# modulo_alimentador_schdoc.net
KiCad netlist of a schematic drawn in Altium Designer
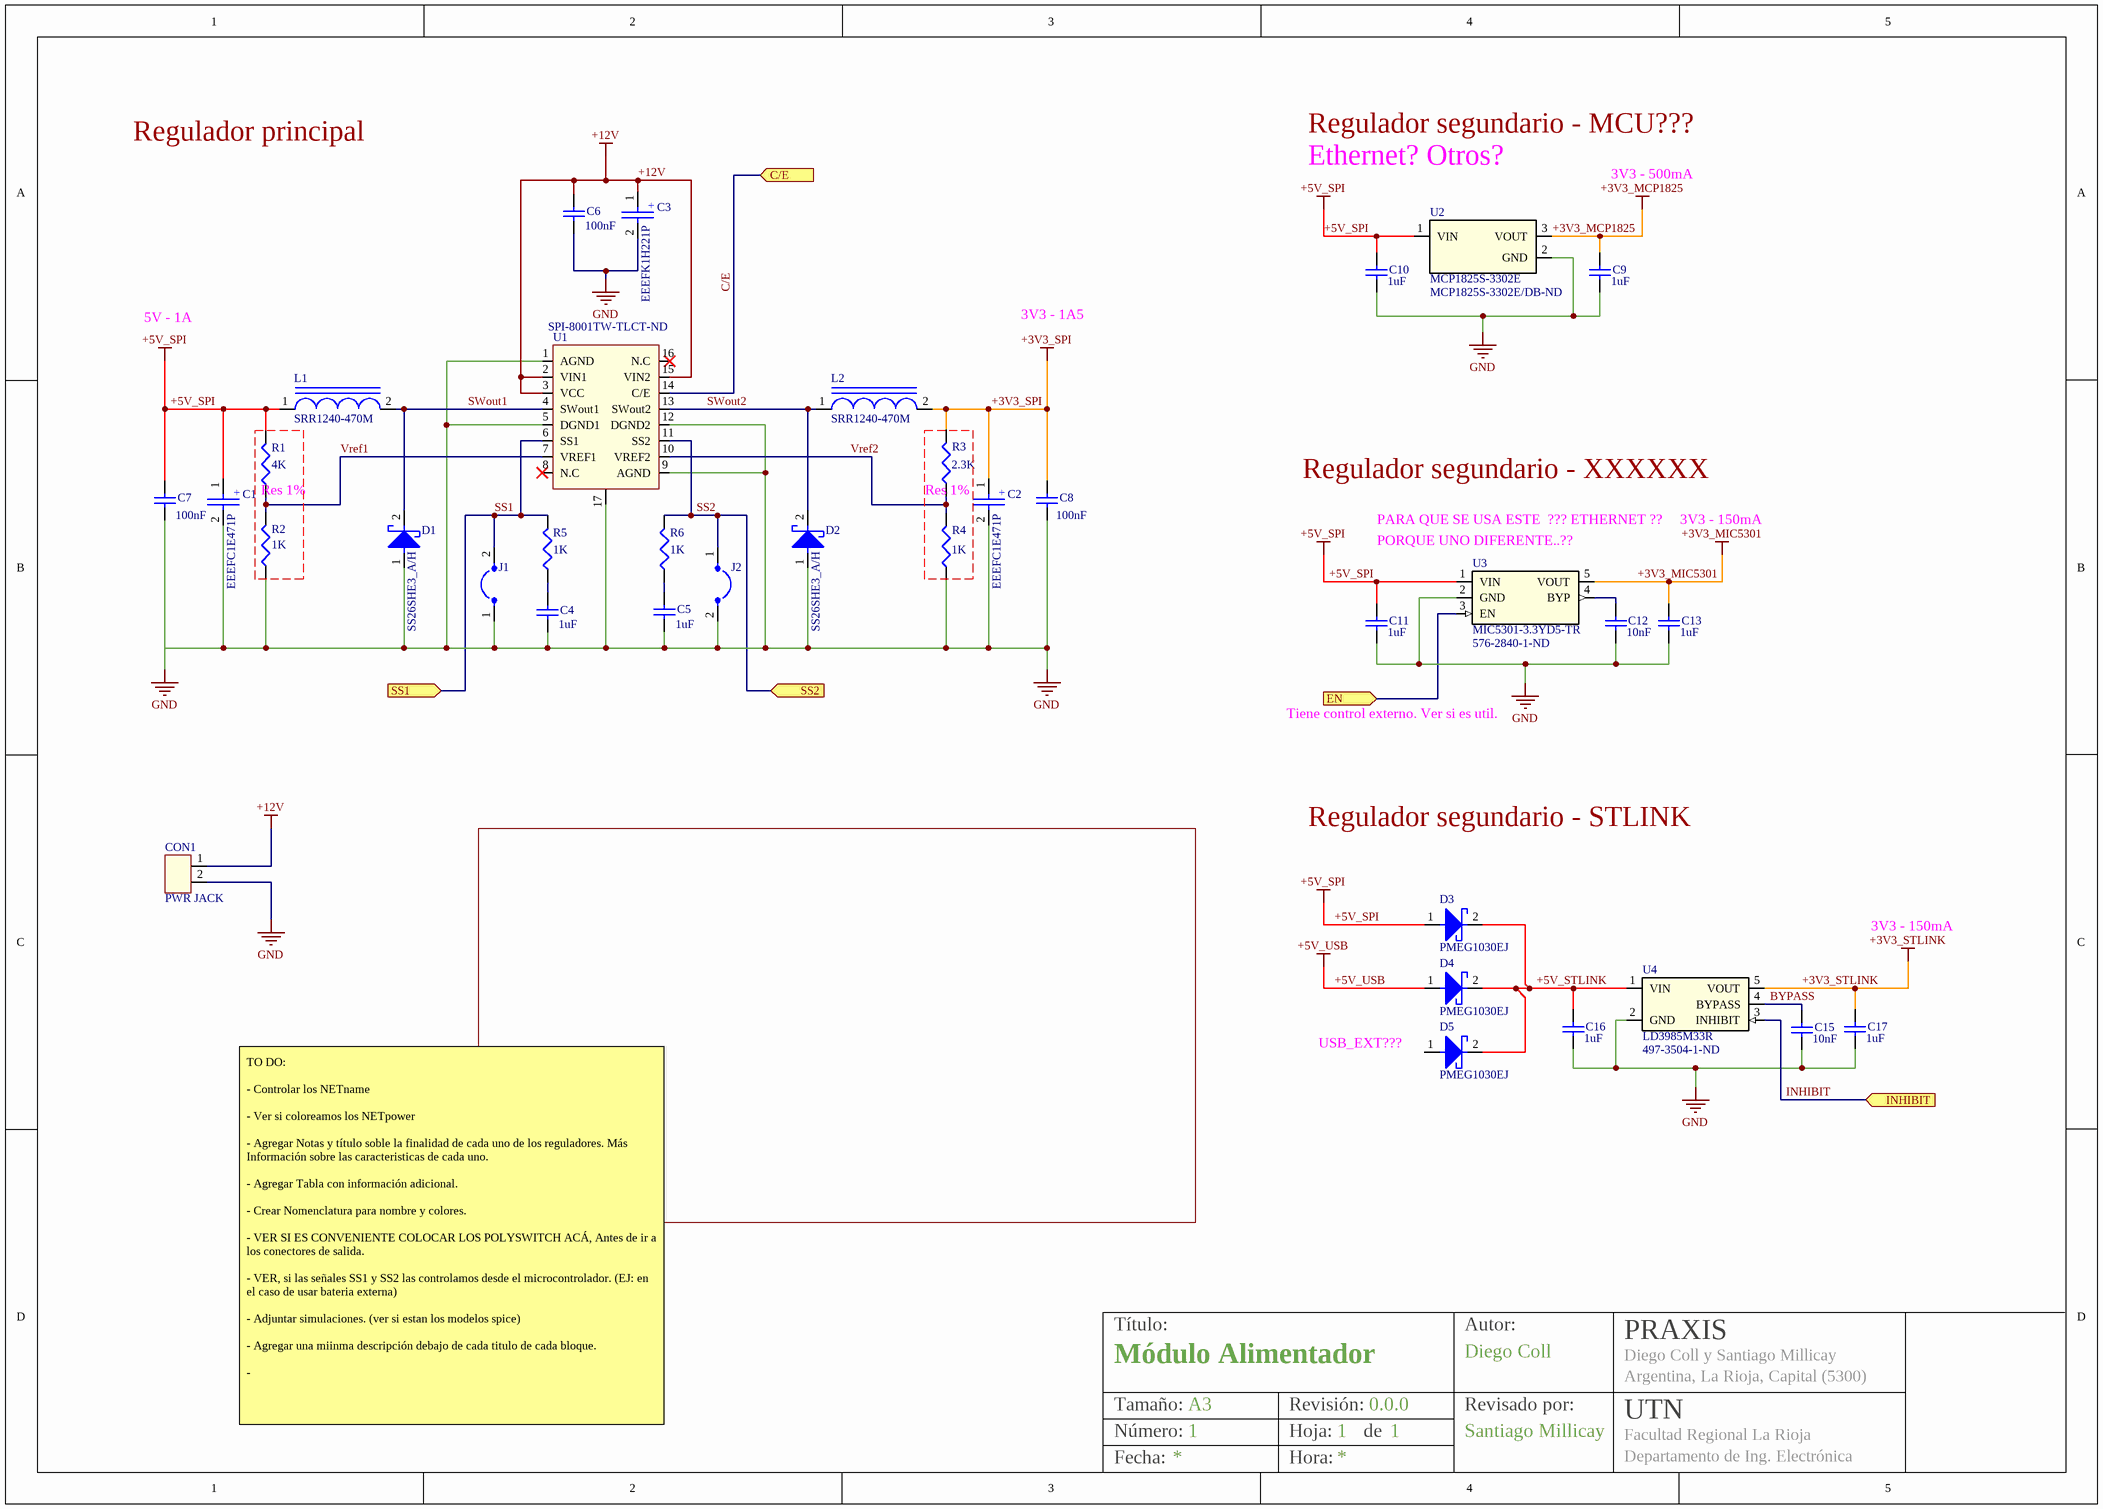
[diagram p0: modulo_alimentador_schdoc.SchDoc]

(export (version "E")
  (design (tool "Eeschema 10.0.6"))
  (components
    (comp (ref "C1")
      (value "EEEFC1E471P")
      (footprint "PCE4009CT")
      (description "Capacitor 470uf electrolitico")
      (fields (field (name "MANUFACTURER") "Panasonic") (field (name "TOLERANCE") "20%"))
      (libsource (lib "schlib_modulo_alimentacion") (part "EEEFC1E471P"))
    )
    (comp (ref "C2")
      (value "EEEFC1E471P")
      (footprint "PCE4009CT")
      (description "Capacitor 470uf electrolitico")
      (fields (field (name "MANUFACTURER") "Panasonic") (field (name "TOLERANCE") "20%"))
      (libsource (lib "schlib_modulo_alimentacion") (part "EEEFC1E471P"))
    )
    (comp (ref "C3")
      (value "EEEFK1H221P")
      (footprint "PCE4009CT")
      (description "Capacitor 220uf electrolitico")
      (fields
        (field (name "MANUFACTURER") "Panasonic")
        (field (name "MANUFACTURER PART NUMBER") "EEE-FK1H221P")
      )
      (libsource (lib "schlib_modulo_alimentacion") (part "EEEFK1H221P"))
    )
    (comp (ref "C4")
      (value "1uF")
      (footprint "1608[0603]")
      (description "Capacitor (Semiconductor SIM Model)")
      (fields (field (name "Comment") "Cap Semi") (field (name "PUBLISHER") "Altium Limited"))
      (libsource (lib "Miscellaneous Devices") (part "Cap Semi"))
    )
    (comp (ref "C5")
      (value "1uF")
      (footprint "1608[0603]")
      (description "Capacitor (Semiconductor SIM Model)")
      (fields (field (name "Comment") "Cap Semi") (field (name "PUBLISHER") "Altium Limited"))
      (libsource (lib "Miscellaneous Devices") (part "Cap Semi"))
    )
    (comp (ref "C6")
      (value "100nF")
      (footprint "1608[0603]")
      (description "Capacitor (Semiconductor SIM Model)")
      (fields (field (name "Comment") "Cap Semi") (field (name "PUBLISHER") "Altium Limited"))
      (libsource (lib "Miscellaneous Devices") (part "Cap Semi"))
    )
    (comp (ref "C7")
      (value "100nF")
      (footprint "1608[0603]")
      (description "Capacitor (Semiconductor SIM Model)")
      (fields (field (name "Comment") "Cap Semi") (field (name "PUBLISHER") "Altium Limited"))
      (libsource (lib "Miscellaneous Devices") (part "Cap Semi"))
    )
    (comp (ref "C8")
      (value "100nF")
      (footprint "1608[0603]")
      (description "Capacitor (Semiconductor SIM Model)")
      (fields (field (name "Comment") "Cap Semi") (field (name "PUBLISHER") "Altium Limited"))
      (libsource (lib "Miscellaneous Devices") (part "Cap Semi"))
    )
    (comp (ref "C9")
      (value "1uF")
      (footprint "1608[0603]")
      (description "Capacitor (Semiconductor SIM Model)")
      (fields (field (name "Comment") "Cap Semi") (field (name "PUBLISHER") "Altium Limited"))
      (libsource (lib "Miscellaneous Devices") (part "Cap Semi"))
    )
    (comp (ref "C10")
      (value "1uF")
      (footprint "1608[0603]")
      (description "Capacitor (Semiconductor SIM Model)")
      (fields (field (name "Comment") "Cap Semi") (field (name "PUBLISHER") "Altium Limited"))
      (libsource (lib "Miscellaneous Devices") (part "Cap Semi"))
    )
    (comp (ref "C11")
      (value "1uF")
      (footprint "1608[0603]")
      (description "Capacitor (Semiconductor SIM Model)")
      (fields (field (name "Comment") "Cap Semi") (field (name "PUBLISHER") "Altium Limited"))
      (libsource (lib "Miscellaneous Devices") (part "Cap Semi"))
    )
    (comp (ref "C12")
      (value "10nF")
      (footprint "1608[0603]")
      (description "Capacitor (Semiconductor SIM Model)")
      (fields (field (name "Comment") "Cap Semi") (field (name "PUBLISHER") "Altium Limited"))
      (libsource (lib "Miscellaneous Devices") (part "Cap Semi"))
    )
    (comp (ref "C13")
      (value "1uF")
      (footprint "1608[0603]")
      (description "Capacitor (Semiconductor SIM Model)")
      (fields (field (name "Comment") "Cap Semi") (field (name "PUBLISHER") "Altium Limited"))
      (libsource (lib "Miscellaneous Devices") (part "Cap Semi"))
    )
    (comp (ref "C15")
      (value "10nF")
      (footprint "1608[0603]")
      (description "Capacitor (Semiconductor SIM Model)")
      (fields (field (name "Comment") "Cap Semi") (field (name "PUBLISHER") "Altium Limited"))
      (libsource (lib "Miscellaneous Devices") (part "Cap Semi"))
    )
    (comp (ref "C16")
      (value "1uF")
      (footprint "1608[0603]")
      (description "Capacitor (Semiconductor SIM Model)")
      (fields (field (name "Comment") "Cap Semi") (field (name "PUBLISHER") "Altium Limited"))
      (libsource (lib "Miscellaneous Devices") (part "Cap Semi"))
    )
    (comp (ref "C17")
      (value "1uF")
      (footprint "1608[0603]")
      (description "Capacitor (Semiconductor SIM Model)")
      (fields (field (name "Comment") "Cap Semi") (field (name "PUBLISHER") "Altium Limited"))
      (libsource (lib "Miscellaneous Devices") (part "Cap Semi"))
    )
    (comp (ref "CON1")
      (value "PWR JACK")
      (footprint "694103107102")
      (description "CONN PWR JACK DC RA SMD")
      (fields
        (field (name "MANUFACTURER") "Wurth Electronics")
        (field (name "MANUFACTURER PART NUMBER") "694103107102")
      )
      (libsource (lib "modulo_alimentador_schlib") (part "694103107102"))
    )
    (comp (ref "D1")
      (value "SS26SHE3_A/H")
      (footprint "SS26SHE3_A/H")
      (description "Diodo schottky 60V 2A")
      (fields
        (field (name "MANUFACTURER") "Vishay")
        (field (name "MANUFACTURER PART NUMBER") "SS26SHE3\"A/H")
      )
      (libsource (lib "schlib_modulo_alimentacion") (part "SS26SHE3_A/H"))
    )
    (comp (ref "D2")
      (value "SS26SHE3_A/H")
      (footprint "SS26SHE3_A/H")
      (description "Diodo schottky 60V 2A")
      (fields
        (field (name "MANUFACTURER") "Vishay")
        (field (name "MANUFACTURER PART NUMBER") "SS26SHE3\"A/H")
      )
      (libsource (lib "schlib_modulo_alimentacion") (part "SS26SHE3_A/H"))
    )
    (comp (ref "D3")
      (value "PMEG1030EJ")
      (footprint "PMEG1030EJ")
      (description "DIODO SCHOTTKY")
      (fields
        (field (name "MANUFACTURER") "Nexperia")
        (field (name "MANUFACTURER PART NUMBER") "PMEG1030EJ,115")
      )
      (libsource (lib "modulo_alimentador_schlib") (part "PMEG1030EJ"))
    )
    (comp (ref "D4")
      (value "PMEG1030EJ")
      (footprint "PMEG1030EJ")
      (description "DIODO SCHOTTKY")
      (fields
        (field (name "MANUFACTURER") "Nexperia")
        (field (name "MANUFACTURER PART NUMBER") "PMEG1030EJ,115")
      )
      (libsource (lib "modulo_alimentador_schlib") (part "PMEG1030EJ"))
    )
    (comp (ref "D5")
      (value "PMEG1030EJ")
      (footprint "PMEG1030EJ")
      (description "DIODO SCHOTTKY")
      (fields
        (field (name "MANUFACTURER") "Nexperia")
        (field (name "MANUFACTURER PART NUMBER") "PMEG1030EJ,115")
      )
      (libsource (lib "modulo_alimentador_schlib") (part "PMEG1030EJ"))
    )
    (comp (ref "J1")
      (value "JUMPER_SMD")
      (footprint "JUMPER_SMD")
      (description "JUMPER SMD Pitch  2.54mm")
      (fields
        (field (name "MANUFACTURER") "Samtec")
        (field (name "MANUFACTURER PART NUMBER") "TSM-102-01-L-SV-TR")
      )
      (libsource (lib "schlib_modulo_alimentacion") (part "JUMPER_SMD"))
    )
    (comp (ref "J2")
      (value "JUMPER_SMD")
      (footprint "JUMPER_SMD")
      (description "JUMPER SMD Pitch  2.54mm")
      (fields
        (field (name "MANUFACTURER") "Samtec")
        (field (name "MANUFACTURER PART NUMBER") "TSM-102-01-L-SV-TR")
      )
      (libsource (lib "schlib_modulo_alimentacion") (part "JUMPER_SMD"))
    )
    (comp (ref "L1")
      (value "SRR1240-470M")
      (footprint "SRR1240-470M")
      (description "Inductor fijo con nucleo.")
      (fields (field (name "MANUFACTURER") "Bourns") (field (name "TOLERANCE") "20%"))
      (libsource (lib "schlib_modulo_alimentacion") (part "SRR1240-470M"))
    )
    (comp (ref "L2")
      (value "SRR1240-470M")
      (footprint "SRR1240-470M")
      (description "Inductor fijo con nucleo.")
      (fields (field (name "MANUFACTURER") "Bourns") (field (name "TOLERANCE") "20%"))
      (libsource (lib "schlib_modulo_alimentacion") (part "SRR1240-470M"))
    )
    (comp (ref "R1")
      (value "4K")
      (footprint "J1-0603")
      (description "Resistor")
      (fields (field (name "Comment") "Res3") (field (name "PUBLISHER") "Altium Limited"))
      (libsource (lib "Miscellaneous Devices") (part "Res3"))
    )
    (comp (ref "R2")
      (value "1K")
      (footprint "J1-0603")
      (description "Resistor")
      (fields (field (name "Comment") "Res3") (field (name "PUBLISHER") "Altium Limited"))
      (libsource (lib "Miscellaneous Devices") (part "Res3"))
    )
    (comp (ref "R3")
      (value "2.3K")
      (footprint "J1-0603")
      (description "Resistor")
      (fields (field (name "Comment") "Res3") (field (name "PUBLISHER") "Altium Limited"))
      (libsource (lib "Miscellaneous Devices") (part "Res3"))
    )
    (comp (ref "R4")
      (value "1K")
      (footprint "J1-0603")
      (description "Resistor")
      (fields (field (name "Comment") "Res3") (field (name "PUBLISHER") "Altium Limited"))
      (libsource (lib "Miscellaneous Devices") (part "Res3"))
    )
    (comp (ref "R5")
      (value "1K")
      (footprint "J1-0603")
      (description "Resistor")
      (fields (field (name "Comment") "Res3") (field (name "PUBLISHER") "Altium Limited"))
      (libsource (lib "Miscellaneous Devices") (part "Res3"))
    )
    (comp (ref "R6")
      (value "1K")
      (footprint "J1-0603")
      (description "Resistor")
      (fields (field (name "Comment") "Res3") (field (name "PUBLISHER") "Altium Limited"))
      (libsource (lib "Miscellaneous Devices") (part "Res3"))
    )
    (comp (ref "U1")
      (value "SPI-8001TW")
      (footprint "SOP127P1050X275_HS-17N")
      (description "IC REG BUCK ADJ 1.5A DL 16-HSOP")
      (fields
        (field (name "MANUFACTURER") "Allegro MicroSystems Sanken")
        (field (name "MANUFACTURER PART NUMBER") "SPI-8001TW-TL")
        (field (name "SUPPLIER PART NUMBER 1") "SPI-8001TW-TLCT-ND")
      )
      (libsource (lib "modulo_alimentador_schlib") (part "SPI-8001TW-TL"))
    )
    (comp (ref "U2")
      (value "MCP1825S-3302E")
      (footprint "MCP1825S-3302E")
      (description "MCP1825 Series 500 mA Low Quiescent Current LDO Regulator - SOT-223-3")
      (fields
        (field (name "MANUFACTURER") "Microchip")
        (field (name "MANUFACTURER PART NUMBER") "MCP1825S-3302E/DB")
        (field (name "SUPPLIER PART NUMBER 1") "MCP1825S-3302E/DB-ND")
      )
      (libsource (lib "modulo_alimentador_schlib") (part "MCP1825S-3302E"))
    )
    (comp (ref "U3")
      (value "MIC5301-3.3YD5-TR")
      (footprint "MIC5301-3.3YD5-TR")
      (fields
        (field (name "MANUFACTURER") "Microchip")
        (field (name "SUPPLIER PART NUMBER 1") "576-2840-1-ND")
      )
      (libsource (lib "modulo_alimentador_schlib") (part "MIC5301-3.3YD5-TR"))
    )
    (comp (ref "U4")
      (value "LD3985M33R")
      (footprint "LD3985M33R")
      (description "LDO Regulator Pos 3.3V 0.55A 5-Pin SOT-23 T/R")
      (fields
        (field (name "MANUFACTURER") "STMicroelectronics")
        (field (name "SUPPLIER PART NUMBER 1") "497-3504-1-ND")
        (field (name "COPYRIGHT") "Copyright (C) 2018 Accelerated Designs. All rights reserved")
      )
      (libsource (lib "modulo_alimentador_schlib") (part "LD3985M33R"))
    )
  )
  (nets
    (net (code "1") (name "+3V3_MCP1825") (class "Default")
      (node (ref "C9") (pin "2") (pinfunction "2_2") (pintype "passive"))
      (node (ref "U2") (pin "3") (pinfunction "VOUT_3") (pintype "power_in"))
    )
    (net (code "2") (name "+3V3_MIC5301") (class "Default")
      (node (ref "C13") (pin "1") (pinfunction "1_1") (pintype "passive"))
      (node (ref "U3") (pin "5") (pinfunction "VOUT_5") (pintype "power_in"))
    )
    (net (code "3") (name "+3V3_SPI") (class "Default")
      (node (ref "C2") (pin "1") (pinfunction "1_1") (pintype "passive"))
      (node (ref "C8") (pin "1") (pinfunction "1_1") (pintype "passive"))
      (node (ref "L2") (pin "2") (pinfunction "2_2") (pintype "passive"))
      (node (ref "R3") (pin "2") (pinfunction "2_2") (pintype "passive"))
    )
    (net (code "4") (name "+3V3_STLINK") (class "Default")
      (node (ref "C17") (pin "1") (pinfunction "1_1") (pintype "passive"))
      (node (ref "U4") (pin "5") (pinfunction "VOUT_5") (pintype "power_in"))
    )
    (net (code "5") (name "+5V_SPI") (class "Default")
      (node (ref "C1") (pin "1") (pinfunction "1_1") (pintype "passive"))
      (node (ref "C10") (pin "2") (pinfunction "2_2") (pintype "passive"))
      (node (ref "C11") (pin "1") (pinfunction "1_1") (pintype "passive"))
      (node (ref "C7") (pin "1") (pinfunction "1_1") (pintype "passive"))
      (node (ref "D3") (pin "1") (pinfunction "A_1") (pintype "passive"))
      (node (ref "L1") (pin "1") (pinfunction "1_1") (pintype "passive"))
      (node (ref "R1") (pin "2") (pinfunction "2_2") (pintype "passive"))
      (node (ref "U2") (pin "1") (pinfunction "VIN_1") (pintype "power_in"))
      (node (ref "U3") (pin "1") (pinfunction "VIN_1") (pintype "power_in"))
    )
    (net (code "6") (name "+5V_USB") (class "Default")
      (node (ref "D4") (pin "1") (pinfunction "A_1") (pintype "passive"))
    )
    (net (code "7") (name "+12V") (class "Default")
      (node (ref "C3") (pin "1") (pinfunction "1_1") (pintype "passive"))
      (node (ref "C6") (pin "1") (pinfunction "1_1") (pintype "passive"))
      (node (ref "CON1") (pin "1") (pinfunction "1_1") (pintype "power_in"))
      (node (ref "U1") (pin "15") (pinfunction "VIN2_15") (pintype "power_in"))
      (node (ref "U1") (pin "2") (pinfunction "VIN1_2") (pintype "power_in"))
      (node (ref "U1") (pin "3") (pinfunction "VCC_3") (pintype "power_in"))
    )
    (net (code "8") (name "/+5V_STLINK") (class "Default")
      (node (ref "C16") (pin "1") (pinfunction "1_1") (pintype "passive"))
      (node (ref "D3") (pin "2") (pinfunction "K_2") (pintype "passive"))
      (node (ref "D4") (pin "2") (pinfunction "K_2") (pintype "passive"))
      (node (ref "D5") (pin "2") (pinfunction "K_2") (pintype "passive"))
      (node (ref "U4") (pin "1") (pinfunction "VIN_1") (pintype "power_in"))
    )
    (net (code "9") (name "/BYPASS") (class "Default")
      (node (ref "C15") (pin "1") (pinfunction "1_1") (pintype "passive"))
      (node (ref "U4") (pin "4") (pinfunction "BYPASS_4") (pintype "passive"))
    )
    (net (code "10") (name "/C{slash}E") (class "Default")
      (node (ref "U1") (pin "14") (pinfunction "C/E_14") (pintype "input"))
    )
    (net (code "11") (name "/EN") (class "Default")
      (node (ref "U3") (pin "3") (pinfunction "EN_3") (pintype "input"))
    )
    (net (code "12") (name "/INHIBIT") (class "Default")
      (node (ref "U4") (pin "3") (pinfunction "INHIBIT_3") (pintype "input"))
    )
    (net (code "13") (name "/SS1") (class "Default")
      (node (ref "J1") (pin "2") (pinfunction "2_2") (pintype "passive"))
      (node (ref "R5") (pin "2") (pinfunction "2_2") (pintype "passive"))
      (node (ref "U1") (pin "6") (pinfunction "SS1_6") (pintype "input"))
    )
    (net (code "14") (name "/SS2") (class "Default")
      (node (ref "J2") (pin "1") (pinfunction "1_1") (pintype "passive"))
      (node (ref "R6") (pin "2") (pinfunction "2_2") (pintype "passive"))
      (node (ref "U1") (pin "11") (pinfunction "SS2_11") (pintype "input"))
    )
    (net (code "15") (name "/SWout1") (class "Default")
      (node (ref "D1") (pin "2") (pinfunction "K_2") (pintype "passive"))
      (node (ref "L1") (pin "2") (pinfunction "2_2") (pintype "passive"))
      (node (ref "U1") (pin "4") (pinfunction "SWout1_4") (pintype "output"))
    )
    (net (code "16") (name "/SWout2") (class "Default")
      (node (ref "D2") (pin "2") (pinfunction "K_2") (pintype "passive"))
      (node (ref "L2") (pin "1") (pinfunction "1_1") (pintype "passive"))
      (node (ref "U1") (pin "13") (pinfunction "SWout2_13") (pintype "output"))
    )
    (net (code "17") (name "/Vref1") (class "Default")
      (node (ref "R1") (pin "1") (pinfunction "1_1") (pintype "passive"))
      (node (ref "R2") (pin "2") (pinfunction "2_2") (pintype "passive"))
      (node (ref "U1") (pin "7") (pinfunction "VREF1_7") (pintype "power_in"))
    )
    (net (code "18") (name "/Vref2") (class "Default")
      (node (ref "R3") (pin "1") (pinfunction "1_1") (pintype "passive"))
      (node (ref "R4") (pin "2") (pinfunction "2_2") (pintype "passive"))
      (node (ref "U1") (pin "10") (pinfunction "VREF2_10") (pintype "power_in"))
    )
    (net (code "19") (name "GND") (class "Default")
      (node (ref "C1") (pin "2") (pinfunction "2_2") (pintype "passive"))
      (node (ref "C10") (pin "1") (pinfunction "1_1") (pintype "passive"))
      (node (ref "C11") (pin "2") (pinfunction "2_2") (pintype "passive"))
      (node (ref "C12") (pin "2") (pinfunction "2_2") (pintype "passive"))
      (node (ref "C13") (pin "2") (pinfunction "2_2") (pintype "passive"))
      (node (ref "C15") (pin "2") (pinfunction "2_2") (pintype "passive"))
      (node (ref "C16") (pin "2") (pinfunction "2_2") (pintype "passive"))
      (node (ref "C17") (pin "2") (pinfunction "2_2") (pintype "passive"))
      (node (ref "C2") (pin "2") (pinfunction "2_2") (pintype "passive"))
      (node (ref "C3") (pin "2") (pinfunction "2_2") (pintype "passive"))
      (node (ref "C4") (pin "1") (pinfunction "1_1") (pintype "passive"))
      (node (ref "C5") (pin "1") (pinfunction "1_1") (pintype "passive"))
      (node (ref "C6") (pin "2") (pinfunction "2_2") (pintype "passive"))
      (node (ref "C7") (pin "2") (pinfunction "2_2") (pintype "passive"))
      (node (ref "C8") (pin "2") (pinfunction "2_2") (pintype "passive"))
      (node (ref "C9") (pin "1") (pinfunction "1_1") (pintype "passive"))
      (node (ref "CON1") (pin "2") (pinfunction "2_2") (pintype "power_in"))
      (node (ref "D1") (pin "1") (pinfunction "A_1") (pintype "passive"))
      (node (ref "D2") (pin "1") (pinfunction "A_1") (pintype "passive"))
      (node (ref "J1") (pin "1") (pinfunction "1_1") (pintype "passive"))
      (node (ref "J2") (pin "2") (pinfunction "2_2") (pintype "passive"))
      (node (ref "R2") (pin "1") (pinfunction "1_1") (pintype "passive"))
      (node (ref "R4") (pin "1") (pinfunction "1_1") (pintype "passive"))
      (node (ref "U1") (pin "1") (pinfunction "AGND_1") (pintype "power_in"))
      (node (ref "U1") (pin "12") (pinfunction "DGND2_12") (pintype "power_in"))
      (node (ref "U1") (pin "17") (pinfunction "Thermal_17") (pintype "power_in"))
      (node (ref "U1") (pin "5") (pinfunction "DGND1_5") (pintype "power_in"))
      (node (ref "U1") (pin "9") (pinfunction "AGND_9") (pintype "power_in"))
      (node (ref "U2") (pin "2") (pinfunction "GND_2") (pintype "power_in"))
      (node (ref "U3") (pin "2") (pinfunction "GND_2") (pintype "power_in"))
      (node (ref "U4") (pin "2") (pinfunction "GND_2") (pintype "power_in"))
    )
    (net (code "20") (name "Net-(C4-Pad2)") (class "Default")
      (node (ref "C4") (pin "2") (pinfunction "2_2") (pintype "passive"))
      (node (ref "R5") (pin "1") (pinfunction "1_1") (pintype "passive"))
    )
    (net (code "21") (name "Net-(C5-Pad2)") (class "Default")
      (node (ref "C5") (pin "2") (pinfunction "2_2") (pintype "passive"))
      (node (ref "R6") (pin "1") (pinfunction "1_1") (pintype "passive"))
    )
    (net (code "22") (name "Net-(U3-BYP)") (class "Default")
      (node (ref "C12") (pin "1") (pinfunction "1_1") (pintype "passive"))
      (node (ref "U3") (pin "4") (pinfunction "BYP_4") (pintype "output"))
    )
    (net (code "23") (name "unconnected-(D5-A-Pad1)") (class "Default")
      (node (ref "D5") (pin "1") (pinfunction "A_1") (pintype "passive"))
    )
    (net (code "24") (name "unconnected-(U1-N.C-Pad8)") (class "Default")
      (node (ref "U1") (pin "8") (pinfunction "N.C_8") (pintype "passive+no_connect"))
    )
    (net (code "25") (name "unconnected-(U1-N.C-Pad16)") (class "Default")
      (node (ref "U1") (pin "16") (pinfunction "N.C_16") (pintype "passive+no_connect"))
    )
  )
)
